# Sheet1.net
KiCad netlist of a schematic drawn in Altium Designer
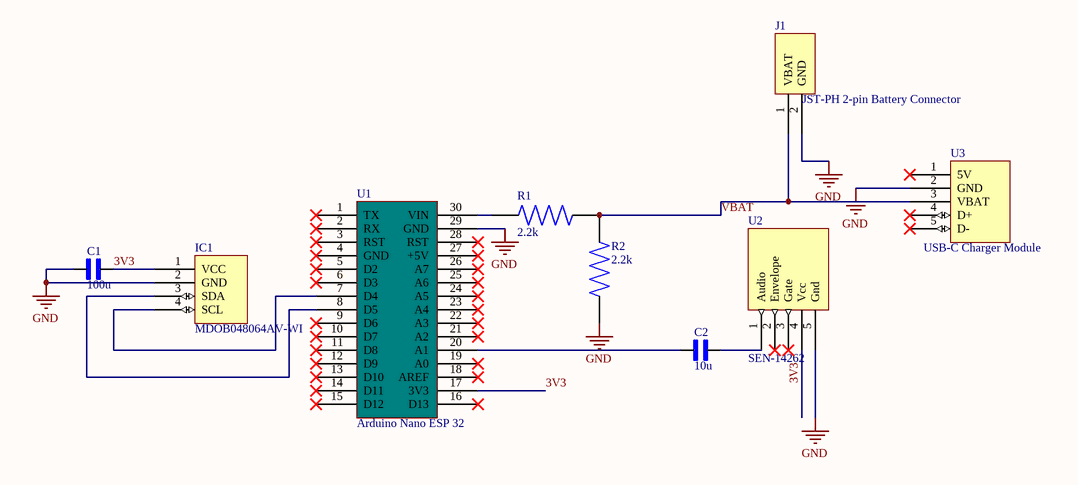
[diagram p0: Sheet1.SchDoc]

(export (version "E")
  (design (tool "Eeschema 10.0.6"))
  (components
    (comp (ref "C1")
      (value "100u")
      (footprint "PcbLib1:CAP")
      (description "capacitor")
      (fields (field (name "MF") "AVX") (field (name "MP") "0805YC103J4T2A"))
      (libsource (lib "Schlib1") (part "cap"))
    )
    (comp (ref "C2")
      (value "10u")
      (footprint "PcbLib1:CAP")
      (description "capacitor")
      (fields (field (name "MF") "AVX") (field (name "MP") "0805YC103J4T2A"))
      (libsource (lib "Schlib1") (part "cap"))
    )
    (comp (ref "IC1")
      (value "MDOB048064AV-WI")
      (footprint "PcbLib1:MDOB048064AV-WI")
      (description "LED")
      (libsource (lib "Schlib1") (part "MDOB048064AV-WI"))
    )
    (comp (ref "J1")
      (value "JST-PH 2-pin Battery Connector")
      (footprint "PcbLib1:JST-PH 2-pin connector")
      (description "JST-PH 2-pin LiPo Battery Connector")
      (libsource (lib "Schlib1") (part "JST-PH 2-pin connector"))
    )
    (comp (ref "R1")
      (value "2.2k")
      (footprint "PcbLib1:RES")
      (description "Resistor")
      (fields (field (name "MF") "Yageo") (field (name "MP") "RC0805FR-07330RL"))
      (libsource (lib "Schlib1") (part "res"))
    )
    (comp (ref "R2")
      (value "2.2k")
      (footprint "PcbLib1:RES")
      (description "Resistor")
      (fields (field (name "MF") "Yageo") (field (name "MP") "RC0805FR-07330RL"))
      (libsource (lib "Schlib1") (part "res"))
    )
    (comp (ref "U1")
      (value "Arduino Nano ESP 32")
      (footprint "PcbLib1:PCBComponent_1 - duplicate")
      (libsource (lib "Schlib1") (part "Component_1_1"))
    )
    (comp (ref "U2")
      (value "SEN-14262")
      (footprint "PcbLib1:SEN-14262")
      (description "Audio sensor")
      (libsource (lib "Schlib1") (part "SEN-14262"))
    )
    (comp (ref "U3")
      (value "USB-C Charger Module")
      (footprint "PcbLib1:ADAFRUIT-4410")
      (description "ADAFRUIT 4410 MICROLIPO USBC MODULE")
      (libsource (lib "Schlib1") (part "ADAFRUIT-4410"))
    )
  )
  (nets
    (net (code "1") (name "/3V3") (class "Default")
      (node (ref "C1") (pin "2") (pinfunction "2_2") (pintype "passive"))
      (node (ref "IC1") (pin "1") (pinfunction "VCC_1") (pintype "power_in"))
      (node (ref "U1") (pin "17") (pinfunction "3V3_17") (pintype "passive"))
      (node (ref "U2") (pin "4") (pinfunction "Vcc_4") (pintype "power_in"))
    )
    (net (code "2") (name "/VBAT") (class "Default")
      (node (ref "J1") (pin "1") (pinfunction "VBAT_1") (pintype "power_in"))
      (node (ref "R1") (pin "2") (pinfunction "2_2") (pintype "passive"))
      (node (ref "R2") (pin "2") (pinfunction "2_2") (pintype "passive"))
      (node (ref "U3") (pin "3") (pinfunction "VBAT_3") (pintype "power_in"))
    )
    (net (code "3") (name "GND") (class "Default")
      (node (ref "C1") (pin "1") (pinfunction "1_1") (pintype "passive"))
      (node (ref "IC1") (pin "2") (pinfunction "GND_2") (pintype "power_in"))
      (node (ref "J1") (pin "2") (pinfunction "GND_2") (pintype "power_in"))
      (node (ref "R2") (pin "1") (pinfunction "1_1") (pintype "passive"))
      (node (ref "U1") (pin "29") (pinfunction "GND_29") (pintype "passive"))
      (node (ref "U2") (pin "5") (pinfunction "Gnd_5") (pintype "power_in"))
      (node (ref "U3") (pin "2") (pinfunction "GND_2") (pintype "power_in"))
    )
    (net (code "4") (name "Net-(IC1-SCL)") (class "Default")
      (node (ref "IC1") (pin "4") (pinfunction "SCL_4") (pintype "bidirectional"))
      (node (ref "U1") (pin "7") (pinfunction "D4_7") (pintype "passive"))
    )
    (net (code "5") (name "Net-(IC1-SDA)") (class "Default")
      (node (ref "IC1") (pin "3") (pinfunction "SDA_3") (pintype "bidirectional"))
      (node (ref "U1") (pin "8") (pinfunction "D5_8") (pintype "passive"))
    )
    (net (code "6") (name "Net-(U1-A1)") (class "Default")
      (node (ref "C2") (pin "1") (pinfunction "1_1") (pintype "passive"))
      (node (ref "U1") (pin "20") (pinfunction "A1_20") (pintype "passive"))
    )
    (net (code "7") (name "Net-(U1-VIN)") (class "Default")
      (node (ref "R1") (pin "1") (pinfunction "1_1") (pintype "passive"))
      (node (ref "U1") (pin "30") (pinfunction "VIN_30") (pintype "passive"))
    )
    (net (code "8") (name "Net-(U2-Audio)") (class "Default")
      (node (ref "C2") (pin "2") (pinfunction "2_2") (pintype "passive"))
      (node (ref "U2") (pin "1") (pinfunction "Audio_1") (pintype "output"))
    )
    (net (code "9") (name "unconnected-(U1-+5V-Pad27)") (class "Default")
      (node (ref "U1") (pin "27") (pinfunction "+5V_27") (pintype "passive+no_connect"))
    )
    (net (code "10") (name "unconnected-(U1-A0-Pad19)") (class "Default")
      (node (ref "U1") (pin "19") (pinfunction "A0_19") (pintype "passive+no_connect"))
    )
    (net (code "11") (name "unconnected-(U1-A2-Pad21)") (class "Default")
      (node (ref "U1") (pin "21") (pinfunction "A2_21") (pintype "passive+no_connect"))
    )
    (net (code "12") (name "unconnected-(U1-A3-Pad22)") (class "Default")
      (node (ref "U1") (pin "22") (pinfunction "A3_22") (pintype "passive+no_connect"))
    )
    (net (code "13") (name "unconnected-(U1-A4-Pad23)") (class "Default")
      (node (ref "U1") (pin "23") (pinfunction "A4_23") (pintype "passive+no_connect"))
    )
    (net (code "14") (name "unconnected-(U1-A5-Pad24)") (class "Default")
      (node (ref "U1") (pin "24") (pinfunction "A5_24") (pintype "passive+no_connect"))
    )
    (net (code "15") (name "unconnected-(U1-A6-Pad25)") (class "Default")
      (node (ref "U1") (pin "25") (pinfunction "A6_25") (pintype "passive+no_connect"))
    )
    (net (code "16") (name "unconnected-(U1-A7-Pad26)") (class "Default")
      (node (ref "U1") (pin "26") (pinfunction "A7_26") (pintype "passive+no_connect"))
    )
    (net (code "17") (name "unconnected-(U1-AREF-Pad18)") (class "Default")
      (node (ref "U1") (pin "18") (pinfunction "AREF_18") (pintype "passive+no_connect"))
    )
    (net (code "18") (name "unconnected-(U1-D2-Pad5)") (class "Default")
      (node (ref "U1") (pin "5") (pinfunction "D2_5") (pintype "passive+no_connect"))
    )
    (net (code "19") (name "unconnected-(U1-D3-Pad6)") (class "Default")
      (node (ref "U1") (pin "6") (pinfunction "D3_6") (pintype "passive+no_connect"))
    )
    (net (code "20") (name "unconnected-(U1-D6-Pad9)") (class "Default")
      (node (ref "U1") (pin "9") (pinfunction "D6_9") (pintype "passive+no_connect"))
    )
    (net (code "21") (name "unconnected-(U1-D7-Pad10)") (class "Default")
      (node (ref "U1") (pin "10") (pinfunction "D7_10") (pintype "passive+no_connect"))
    )
    (net (code "22") (name "unconnected-(U1-D8-Pad11)") (class "Default")
      (node (ref "U1") (pin "11") (pinfunction "D8_11") (pintype "passive+no_connect"))
    )
    (net (code "23") (name "unconnected-(U1-D9-Pad12)") (class "Default")
      (node (ref "U1") (pin "12") (pinfunction "D9_12") (pintype "passive+no_connect"))
    )
    (net (code "24") (name "unconnected-(U1-D10-Pad13)") (class "Default")
      (node (ref "U1") (pin "13") (pinfunction "D10_13") (pintype "passive+no_connect"))
    )
    (net (code "25") (name "unconnected-(U1-D11-Pad14)") (class "Default")
      (node (ref "U1") (pin "14") (pinfunction "D11_14") (pintype "passive+no_connect"))
    )
    (net (code "26") (name "unconnected-(U1-D12-Pad15)") (class "Default")
      (node (ref "U1") (pin "15") (pinfunction "D12_15") (pintype "passive+no_connect"))
    )
    (net (code "27") (name "unconnected-(U1-D13-Pad16)") (class "Default")
      (node (ref "U1") (pin "16") (pinfunction "D13_16") (pintype "passive+no_connect"))
    )
    (net (code "28") (name "unconnected-(U1-GND-Pad4)") (class "Default")
      (node (ref "U1") (pin "4") (pinfunction "GND_4") (pintype "passive+no_connect"))
    )
    (net (code "29") (name "unconnected-(U1-RST-Pad3)") (class "Default")
      (node (ref "U1") (pin "3") (pinfunction "RST_3") (pintype "passive+no_connect"))
    )
    (net (code "30") (name "unconnected-(U1-RST-Pad28)") (class "Default")
      (node (ref "U1") (pin "28") (pinfunction "RST_28") (pintype "passive+no_connect"))
    )
    (net (code "31") (name "unconnected-(U1-RX-Pad2)") (class "Default")
      (node (ref "U1") (pin "2") (pinfunction "RX_2") (pintype "passive+no_connect"))
    )
    (net (code "32") (name "unconnected-(U1-TX-Pad1)") (class "Default")
      (node (ref "U1") (pin "1") (pinfunction "TX_1") (pintype "passive+no_connect"))
    )
    (net (code "33") (name "unconnected-(U2-Envelope-Pad2)") (class "Default")
      (node (ref "U2") (pin "2") (pinfunction "Envelope_2") (pintype "output+no_connect"))
    )
    (net (code "34") (name "unconnected-(U2-Gate-Pad3)") (class "Default")
      (node (ref "U2") (pin "3") (pinfunction "Gate_3") (pintype "output+no_connect"))
    )
    (net (code "35") (name "unconnected-(U3-5V-Pad1)") (class "Default")
      (node (ref "U3") (pin "1") (pinfunction "5V_1") (pintype "power_in+no_connect"))
    )
    (net (code "36") (name "unconnected-(U3-D+-Pad4)") (class "Default")
      (node (ref "U3") (pin "4") (pinfunction "D+_4") (pintype "bidirectional+no_connect"))
    )
    (net (code "37") (name "unconnected-(U3-D--Pad5)") (class "Default")
      (node (ref "U3") (pin "5") (pinfunction "D-_5") (pintype "bidirectional+no_connect"))
    )
  )
)
